# OSP_Carrier_V7_Release_SD.net
KiCad netlist of a schematic drawn in Altium Designer
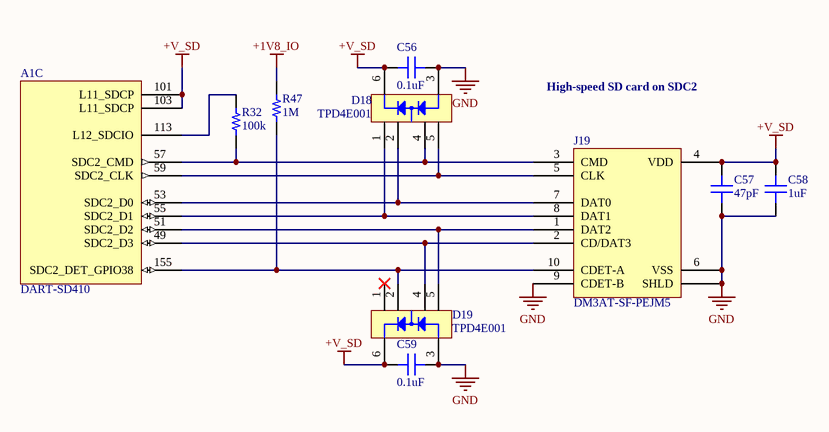
[diagram p0: OSP_Carrier_V7_Release_SD.SchDoc]

(export (version "E")
  (design (tool "Eeschema 10.0.6"))
  (components
    (comp (ref "A1")
      (value "DART-SD410")
      (footprint "DART-SD410")
      (description "Variscite DART-SD410 System on Module")
      (libsource (lib "DART-SD410") (part "DART-SD410"))
    )
    (comp (ref "C56")
      (value "0.1uF")
      (footprint "CAP 0402/1005")
      (description "CAP CER 0.1UF 50V X7R 0402")
      (fields
        (field (name "PART NUMBER") "C1005X7R1H104K050BB")
        (field (name "MANUFACTURER") "TDK Corporation")
      )
      (libsource (lib "Celestial Library Database") (part "Capacitor"))
    )
    (comp (ref "C57")
      (value "47pF")
      (footprint "CAP 0402/1005")
      (description "CAP CER 47PF 50V C0G 0402")
      (fields
        (field (name "PART NUMBER") "C1005C0G1H470G050BA")
        (field (name "MANUFACTURER") "TDK Corporation")
      )
      (libsource (lib "Celestial Library Database") (part "Capacitor"))
    )
    (comp (ref "C58")
      (value "1uF")
      (footprint "CAP 0603/1608")
      (description "CAP CER 1UF 25V X7R 0603")
      (fields
        (field (name "PART NUMBER") "C1608X7R1E105K080AB")
        (field (name "MANUFACTURER") "TDK Corporation")
      )
      (libsource (lib "Celestial Library Database") (part "Capacitor"))
    )
    (comp (ref "C59")
      (value "0.1uF")
      (footprint "CAP 0402/1005")
      (description "CAP CER 0.1UF 50V X7R 0402")
      (fields
        (field (name "PART NUMBER") "C1005X7R1H104K050BB")
        (field (name "MANUFACTURER") "TDK Corporation")
      )
      (libsource (lib "Celestial Library Database") (part "Capacitor"))
    )
    (comp (ref "D18")
      (value "TPD4E001")
      (footprint "TI_SOT-563_DRL")
      (description "TI TPD4E001 4-channel TVS ESD protection diodes")
      (libsource (lib "") (part "TI_TPD4E001_1"))
    )
    (comp (ref "D19")
      (value "TPD4E001")
      (footprint "TI_SOT-563_DRL")
      (description "TI TPD4E001 4-channel TVS ESD protection diodes")
      (libsource (lib "OSP_Symbols") (part "TI_TPD4E001"))
    )
    (comp (ref "J19")
      (value "DM3AT-SF-PEJM5")
      (footprint "HIROSE DM3AT-SF-PEJM5")
      (description "CONN MICRO SD CARD PUSH-PUSH R/A")
      (fields (field (name "MANUFACTURER") "Hirose Electric Co Ltd"))
      (libsource (lib "Celestial Library Database") (part "Hirose DM3 MicroSD"))
    )
    (comp (ref "R32")
      (value "100k")
      (footprint "RES 0402/1005")
      (description "RES SMD 100K OHM 1% 1/10W 0402")
      (fields (field (name "PART NUMBER") "ERJ-2RKF1003X"))
      (libsource (lib "Celestial Library Database") (part "Resistor"))
    )
    (comp (ref "R47")
      (value "1M")
      (footprint "RES 0402/1005")
      (description "RES SMD 1M OHM 1% 1/10W 0402")
      (fields
        (field (name "PART NUMBER") "ERJ-2RKF1004X")
        (field (name "MANUFACTURER") "Panasonic Electronic Components")
      )
      (libsource (lib "Celestial Library Database") (part "Resistor"))
    )
  )
  (nets
    (net (code "1") (name "+1V8_IO") (class "Default")
      (node (ref "R47") (pin "2") (pinfunction "2_2") (pintype "passive"))
    )
    (net (code "2") (name "+V_SD") (class "Default")
      (node (ref "A1") (pin "101") (pinfunction "L11_SDCP_101") (pintype "power_in"))
      (node (ref "A1") (pin "103") (pinfunction "L11_SDCP_103") (pintype "power_in"))
      (node (ref "C56") (pin "2") (pinfunction "2_2") (pintype "passive"))
      (node (ref "C57") (pin "2") (pinfunction "2_2") (pintype "passive"))
      (node (ref "C58") (pin "2") (pinfunction "2_2") (pintype "passive"))
      (node (ref "C59") (pin "2") (pinfunction "2_2") (pintype "passive"))
      (node (ref "D18") (pin "6") (pintype "power_in"))
      (node (ref "D19") (pin "6") (pintype "power_in"))
      (node (ref "J19") (pin "4") (pinfunction "VDD_4") (pintype "passive"))
    )
    (net (code "3") (name "GND") (class "Default")
      (node (ref "C56") (pin "1") (pinfunction "1_1") (pintype "passive"))
      (node (ref "C57") (pin "1") (pinfunction "1_1") (pintype "passive"))
      (node (ref "C58") (pin "1") (pinfunction "1_1") (pintype "passive"))
      (node (ref "C59") (pin "1") (pinfunction "1_1") (pintype "passive"))
      (node (ref "D18") (pin "3") (pintype "power_in"))
      (node (ref "D19") (pin "3") (pintype "power_in"))
      (node (ref "J19") (pin "6") (pinfunction "VSS_6") (pintype "passive"))
      (node (ref "J19") (pin "9") (pinfunction "CDET-B_9") (pintype "passive"))
      (node (ref "J19") (pin "S") (pinfunction "SHLD_S") (pintype "passive"))
    )
    (net (code "4") (name "Net-(A1C-L12_SDCIO)") (class "Default")
      (node (ref "A1") (pin "113") (pinfunction "L12_SDCIO_113") (pintype "power_in"))
      (node (ref "R32") (pin "2") (pinfunction "2_2") (pintype "passive"))
    )
    (net (code "5") (name "Net-(A1C-SDC2_CLK)") (class "Default")
      (node (ref "A1") (pin "59") (pinfunction "SDC2_CLK_59") (pintype "output"))
      (node (ref "D18") (pin "5") (pintype "passive"))
      (node (ref "J19") (pin "5") (pinfunction "CLK_5") (pintype "passive"))
    )
    (net (code "6") (name "Net-(A1C-SDC2_CMD)") (class "Default")
      (node (ref "A1") (pin "57") (pinfunction "SDC2_CMD_57") (pintype "output"))
      (node (ref "D18") (pin "4") (pintype "passive"))
      (node (ref "J19") (pin "3") (pinfunction "CMD_3") (pintype "passive"))
      (node (ref "R32") (pin "1") (pinfunction "1_1") (pintype "passive"))
    )
    (net (code "7") (name "Net-(A1C-SDC2_D0)") (class "Default")
      (node (ref "A1") (pin "53") (pinfunction "SDC2_D0_53") (pintype "bidirectional"))
      (node (ref "D18") (pin "2") (pintype "passive"))
      (node (ref "J19") (pin "7") (pinfunction "DAT0_7") (pintype "passive"))
    )
    (net (code "8") (name "Net-(A1C-SDC2_D1)") (class "Default")
      (node (ref "A1") (pin "55") (pinfunction "SDC2_D1_55") (pintype "bidirectional"))
      (node (ref "D18") (pin "1") (pintype "passive"))
      (node (ref "J19") (pin "8") (pinfunction "DAT1_8") (pintype "passive"))
    )
    (net (code "9") (name "Net-(A1C-SDC2_D2)") (class "Default")
      (node (ref "A1") (pin "51") (pinfunction "SDC2_D2_51") (pintype "bidirectional"))
      (node (ref "D19") (pin "5") (pintype "passive"))
      (node (ref "J19") (pin "1") (pinfunction "DAT2_1") (pintype "passive"))
    )
    (net (code "10") (name "Net-(A1C-SDC2_D3)") (class "Default")
      (node (ref "A1") (pin "49") (pinfunction "SDC2_D3_49") (pintype "bidirectional"))
      (node (ref "D19") (pin "4") (pintype "passive"))
      (node (ref "J19") (pin "2") (pinfunction "CD/DAT3_2") (pintype "passive"))
    )
    (net (code "11") (name "Net-(A1C-SDC2_DET_GPIO38)") (class "Default")
      (node (ref "A1") (pin "155") (pinfunction "SDC2_DET_GPIO38_155") (pintype "bidirectional"))
      (node (ref "D19") (pin "2") (pintype "passive"))
      (node (ref "J19") (pin "10") (pinfunction "CDET-A_10") (pintype "passive"))
      (node (ref "R47") (pin "1") (pinfunction "1_1") (pintype "passive"))
    )
    (net (code "12") (name "unconnected-(D19-Pad1)") (class "Default")
      (node (ref "D19") (pin "1") (pintype "passive+no_connect"))
    )
  )
)
